# 3_Communication.net
KiCad netlist of a schematic drawn in Altium Designer
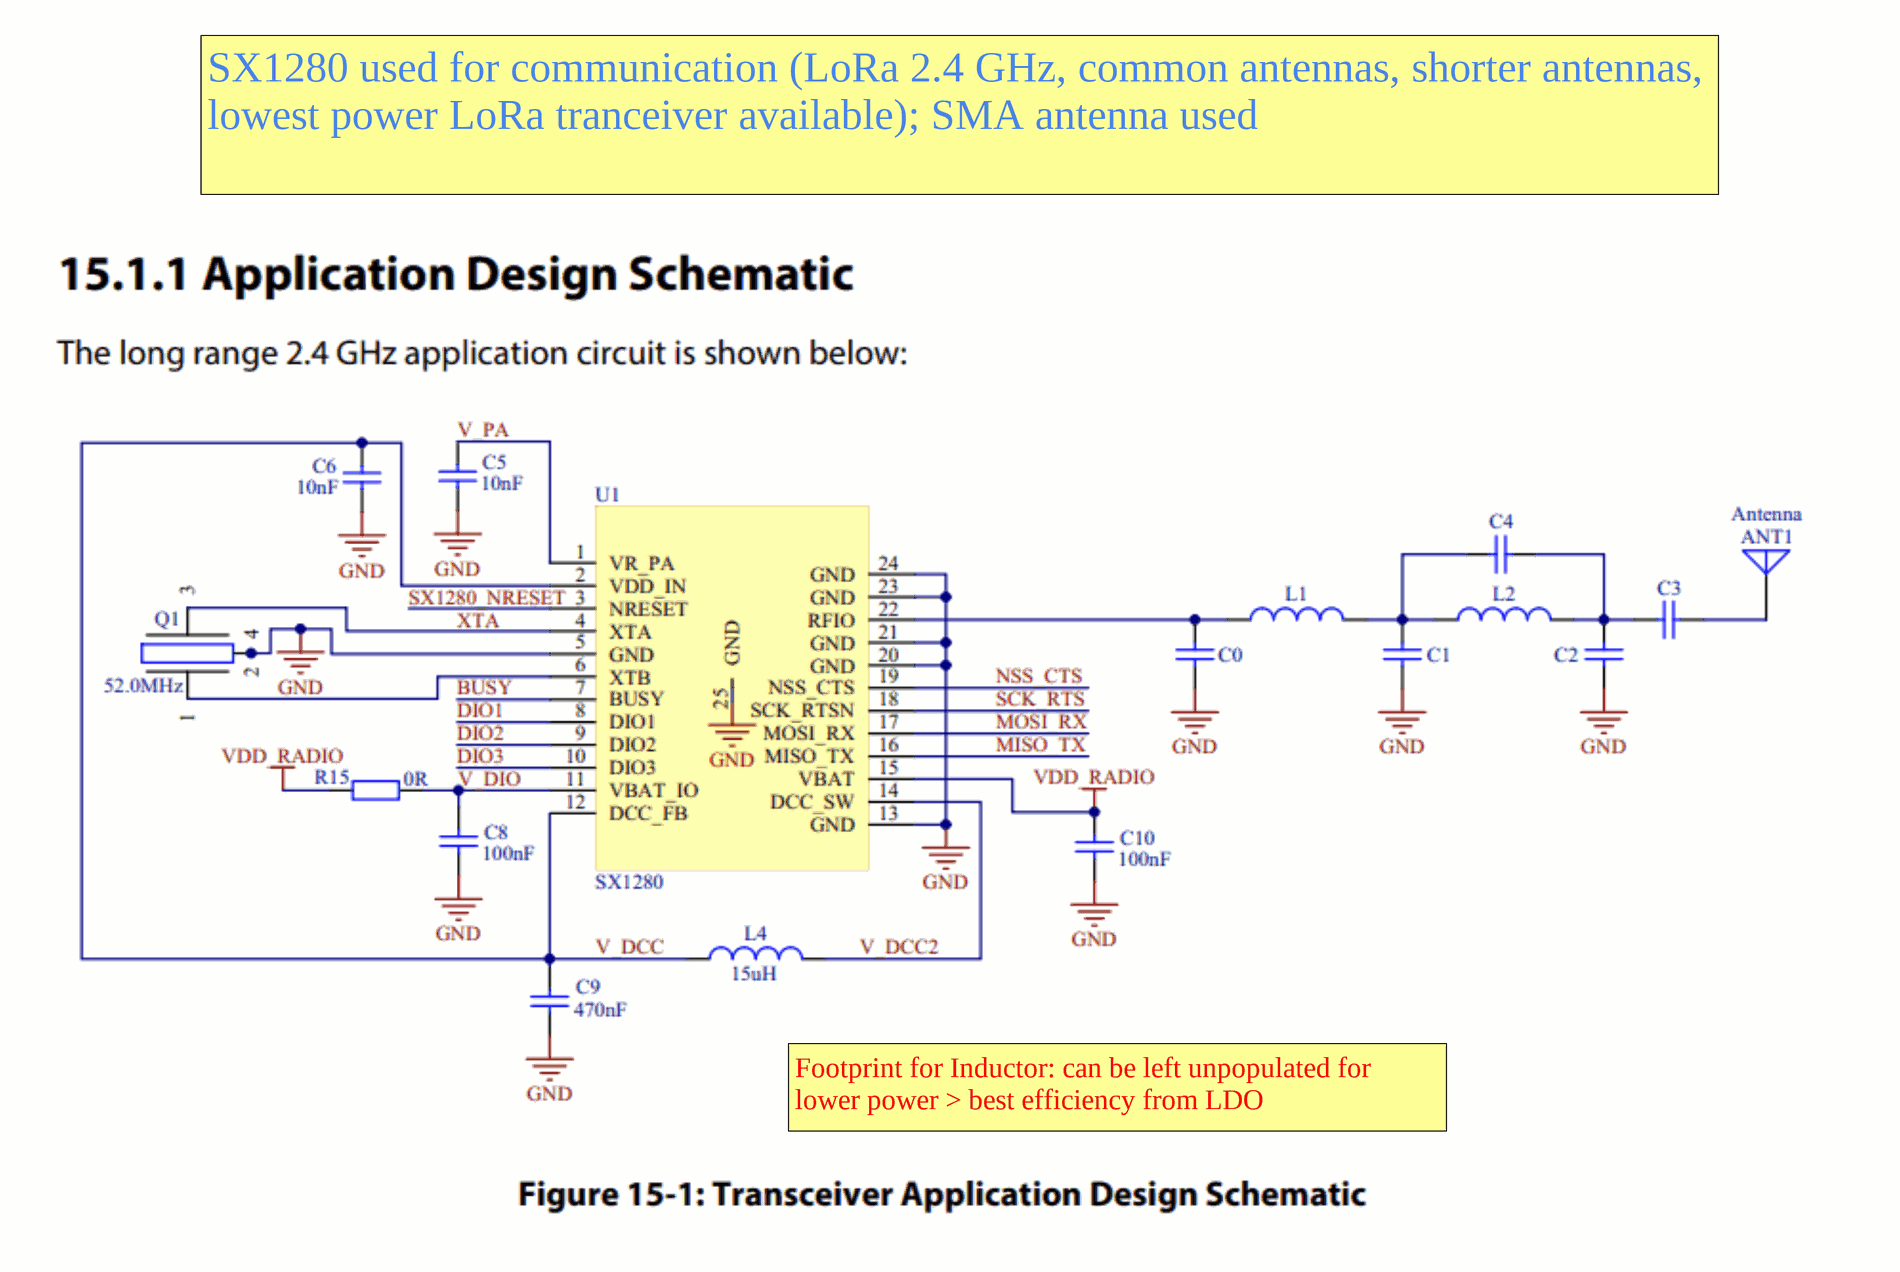
[diagram p0: 3_Communication.SchDoc, left]
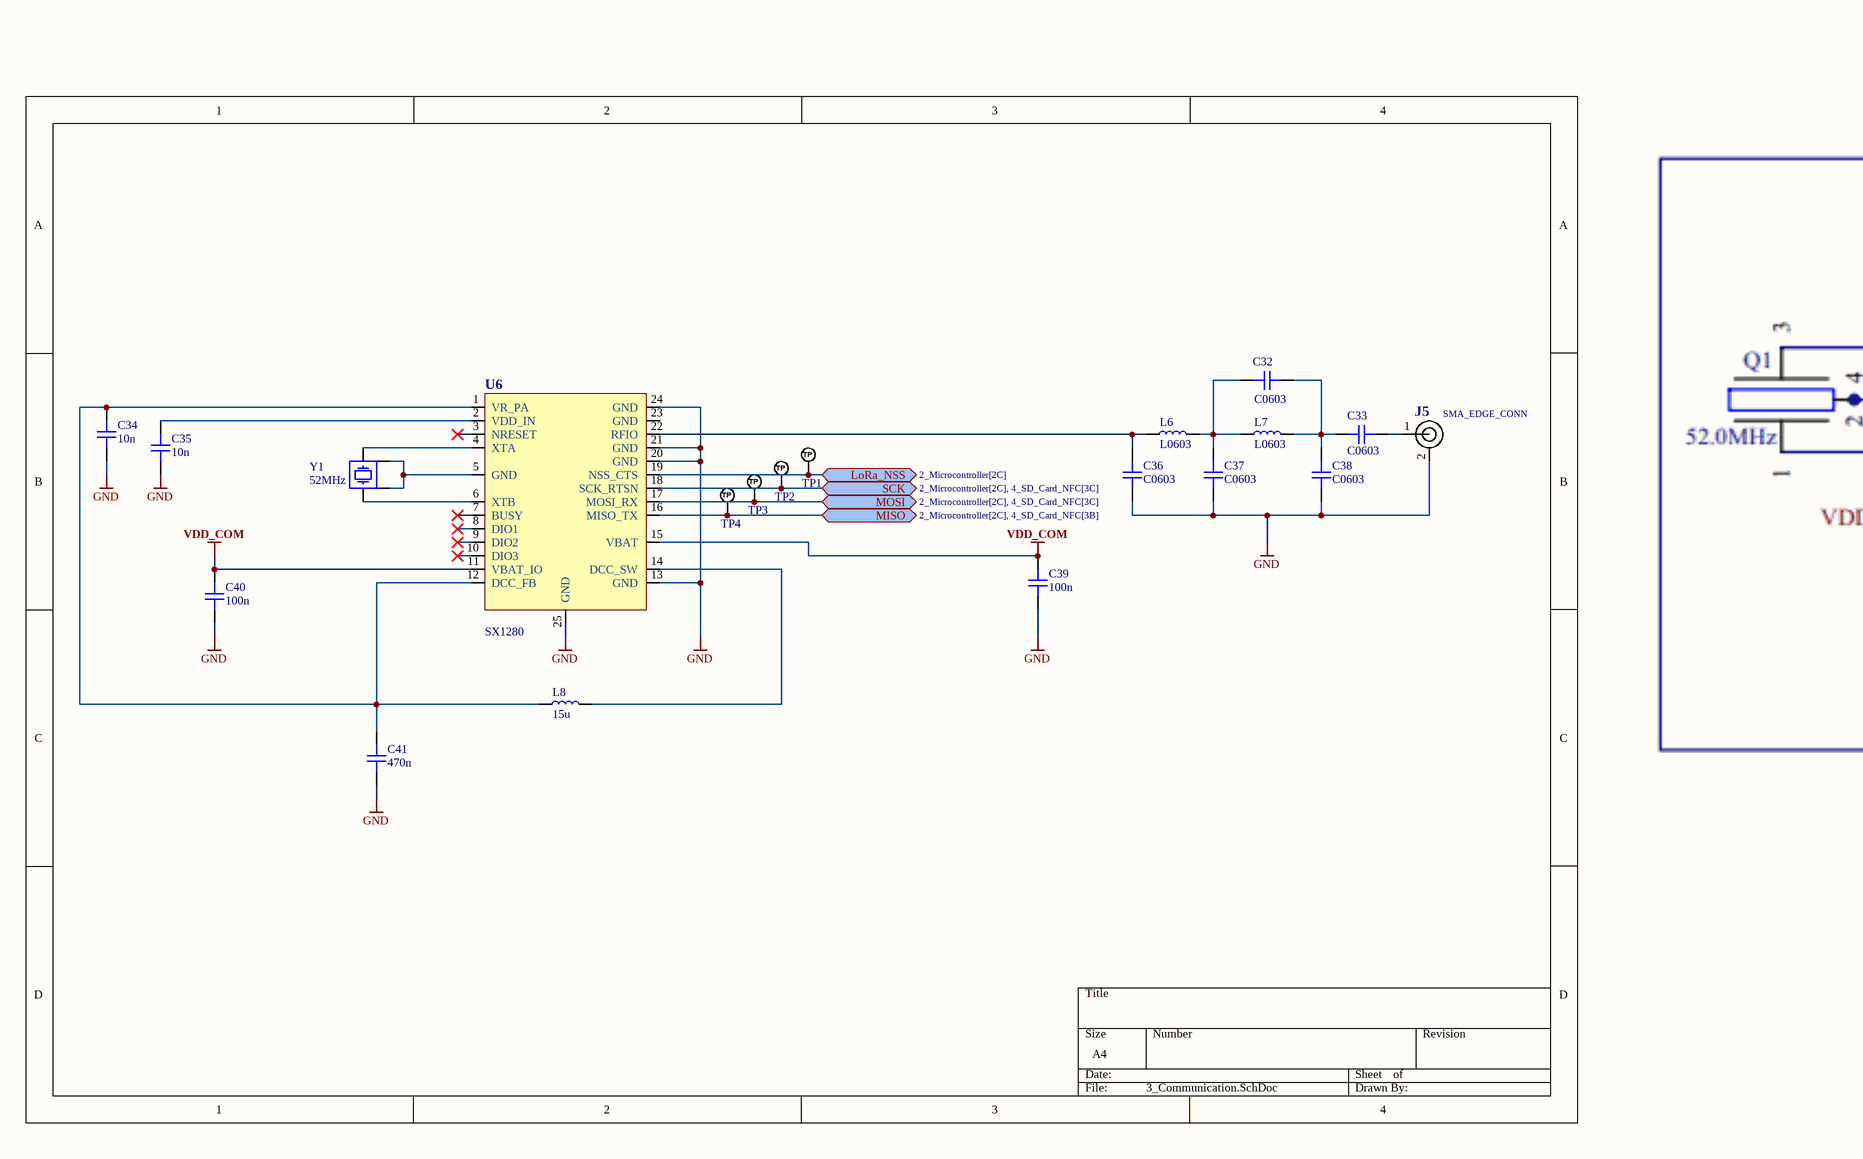
[diagram p1: 3_Communication.SchDoc, middle]
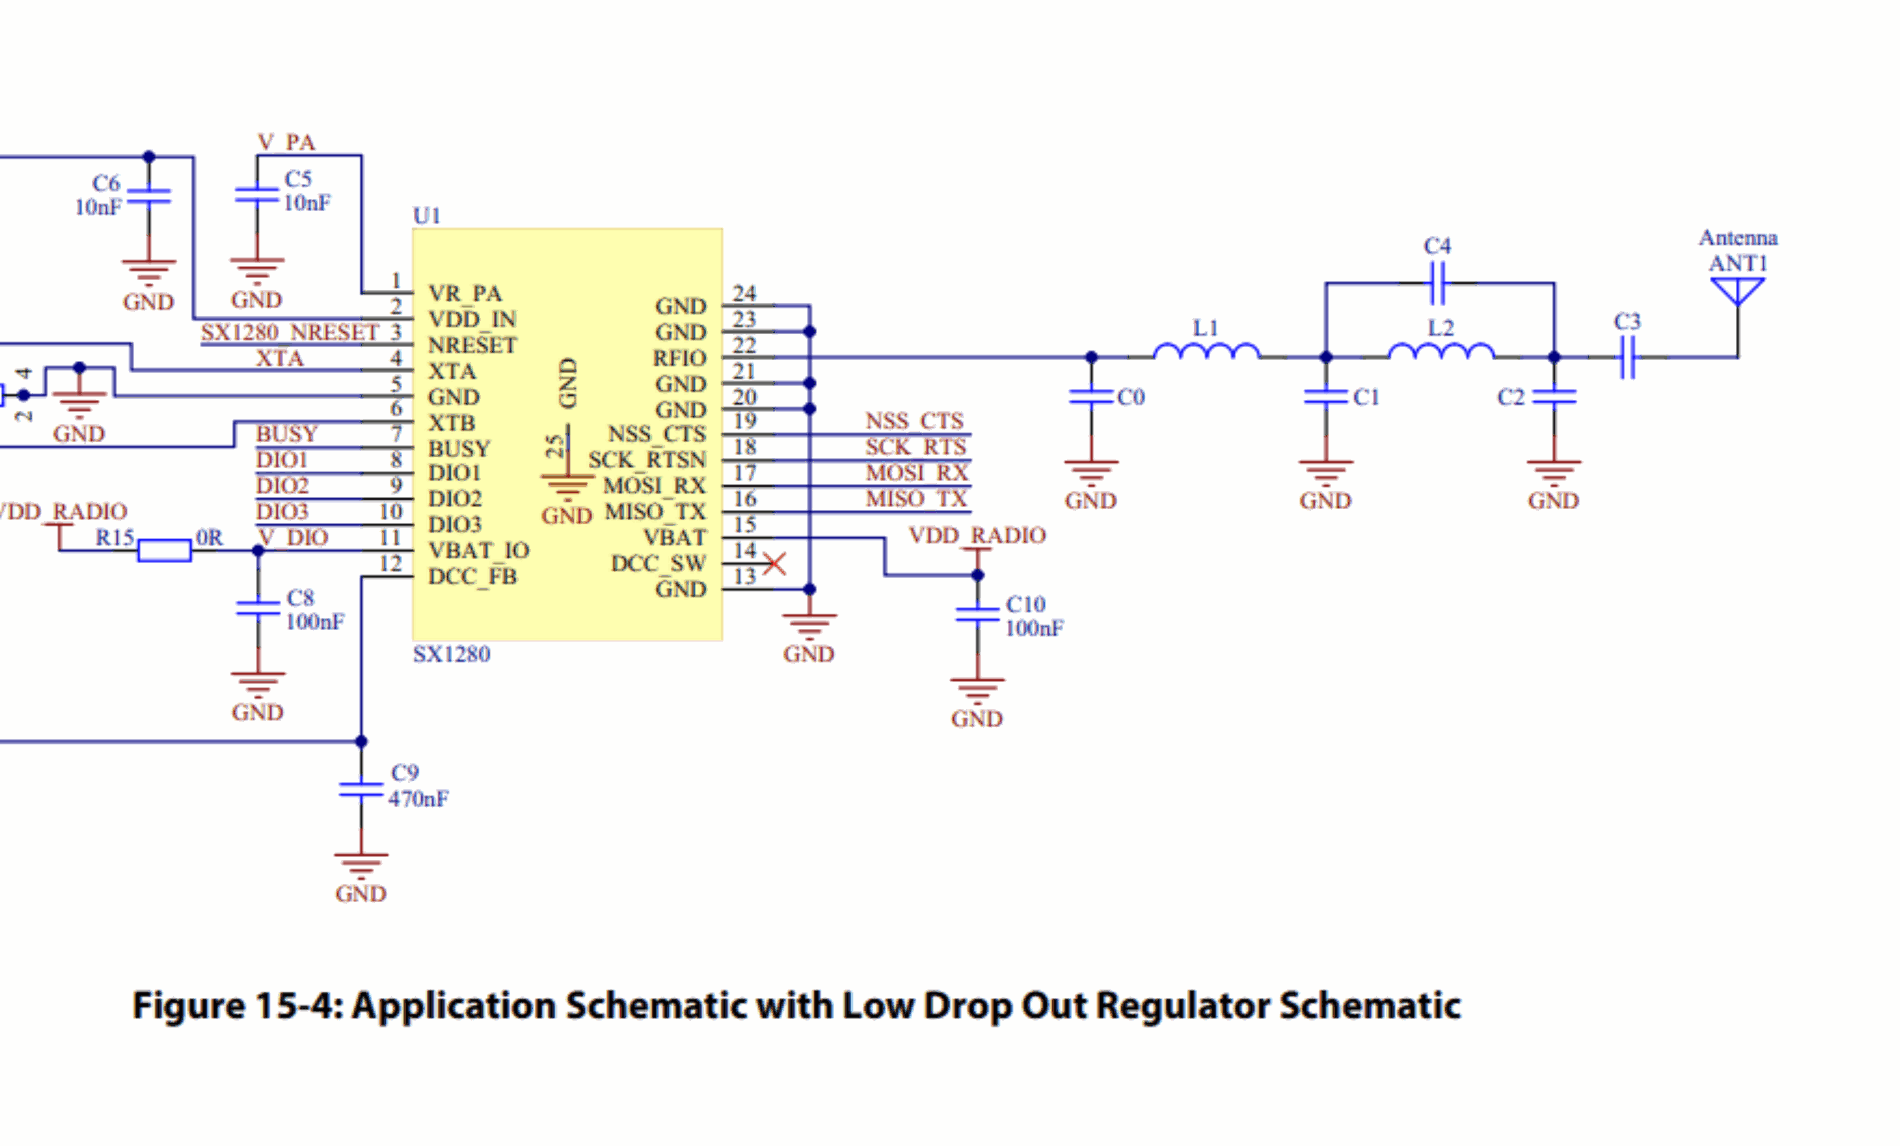
[diagram p2: 3_Communication.SchDoc, right]

(export (version "E")
  (design (tool "Eeschema 10.0.6"))
  (components
    (comp (ref "C32")
      (value "C0603")
      (footprint "CAP_0603")
      (description "Capacitor SMD 0603")
      (libsource (lib "Schlib_H2") (part "CAP_0603"))
    )
    (comp (ref "C33")
      (value "C0603")
      (footprint "CAP_0603")
      (description "Capacitor SMD 0603")
      (libsource (lib "Schlib_H2") (part "CAP_0603"))
    )
    (comp (ref "C34")
      (value "10n")
      (footprint "CAP_0603")
      (description "Capacitor SMD 0603")
      (libsource (lib "Schlib_H2") (part "CAP_0603"))
    )
    (comp (ref "C35")
      (value "10n")
      (footprint "CAP_0603")
      (description "Capacitor SMD 0603")
      (libsource (lib "Schlib_H2") (part "CAP_0603"))
    )
    (comp (ref "C36")
      (value "C0603")
      (footprint "CAP_0603")
      (description "Capacitor SMD 0603")
      (libsource (lib "Schlib_H2") (part "CAP_0603"))
    )
    (comp (ref "C37")
      (value "C0603")
      (footprint "CAP_0603")
      (description "Capacitor SMD 0603")
      (libsource (lib "Schlib_H2") (part "CAP_0603"))
    )
    (comp (ref "C38")
      (value "C0603")
      (footprint "CAP_0603")
      (description "Capacitor SMD 0603")
      (libsource (lib "Schlib_H2") (part "CAP_0603"))
    )
    (comp (ref "C39")
      (value "100n")
      (footprint "CAP_0603")
      (description "Capacitor SMD 0603")
      (libsource (lib "Schlib_H2") (part "CAP_0603"))
    )
    (comp (ref "C40")
      (value "100n")
      (footprint "CAP_0603")
      (description "Capacitor SMD 0603")
      (libsource (lib "Schlib_H2") (part "CAP_0603"))
    )
    (comp (ref "C41")
      (value "470n")
      (footprint "CAP_0603")
      (description "Capacitor SMD 0603")
      (libsource (lib "Schlib_H2") (part "CAP_0603"))
    )
    (comp (ref "J5")
      (value "SMA_EDGE_CONN")
      (footprint "CON-SMA-EDGE-S")
      (description "RF Connector SMA Female 50 Ohms 18 GHz PCB Edge Mount")
      (fields
        (field (name "MANUFACTURER") "RF Solutions")
        (field (name "MANUFACTURER PART NUMBER") "CON-SMA-EDGE-S")
      )
      (libsource (lib "Schlib_H2") (part "CON-SMA-EDGE-S"))
    )
    (comp (ref "L6")
      (value "L0603")
      (footprint "IND_0603")
      (description "Inductor SMD 0603")
      (libsource (lib "Schlib_H2") (part "IND_0603"))
    )
    (comp (ref "L7")
      (value "L0603")
      (footprint "IND_0603")
      (description "Inductor SMD 0603")
      (libsource (lib "Schlib_H2") (part "IND_0603"))
    )
    (comp (ref "L8")
      (value "15u")
      (footprint "IND_0603")
      (description "Inductor SMD 0603")
      (libsource (lib "Schlib_H2") (part "IND_0603"))
    )
    (comp (ref "TP1")
      (value "TP_NOBOM")
      (footprint "PAD_RND_1MM")
      (description "Test Point Round 1mm (NO BOM)")
      (libsource (lib "Schlib_H2") (part "TEST_POINT_RND_1MM"))
    )
    (comp (ref "TP2")
      (value "TP_NOBOM")
      (footprint "PAD_RND_1MM")
      (description "Test Point Round 1mm (NO BOM)")
      (libsource (lib "Schlib_H2") (part "TEST_POINT_RND_1MM"))
    )
    (comp (ref "TP3")
      (value "TP_NOBOM")
      (footprint "PAD_RND_1MM")
      (description "Test Point Round 1mm (NO BOM)")
      (libsource (lib "Schlib_H2") (part "TEST_POINT_RND_1MM"))
    )
    (comp (ref "TP4")
      (value "TP_NOBOM")
      (footprint "PAD_RND_1MM")
      (description "Test Point Round 1mm (NO BOM)")
      (libsource (lib "Schlib_H2") (part "TEST_POINT_RND_1MM"))
    )
    (comp (ref "U6")
      (value "SX1280")
      (description "Low power LoRa transceiver operating at 2.4GHz with ranging capability")
      (libsource (lib "Schlib_H2") (part "SX1280"))
    )
    (comp (ref "Y1")
      (value "52MHz")
      (footprint "XTAL_3225")
      (description "Crystal")
      (fields
        (field (name "MANUFACTURER") "Epson")
        (field (name "MANUFACTURER PART NUMBER") "TSX-3225 24.0000MF15X-AC")
      )
      (libsource (lib "Schlib_H2") (part "Crystal"))
    )
  )
  (nets
    (net (code "1") (name "/LoRa_NSS") (class "Default")
      (node (ref "TP1") (pin "1") (pinfunction "TP_1") (pintype "passive"))
      (node (ref "U6") (pin "19") (pinfunction "NSS_CTS_19") (pintype "passive"))
    )
    (net (code "2") (name "/MISO") (class "Default")
      (node (ref "TP4") (pin "1") (pinfunction "TP_1") (pintype "passive"))
      (node (ref "U6") (pin "16") (pinfunction "MISO_TX_16") (pintype "passive"))
    )
    (net (code "3") (name "/MOSI") (class "Default")
      (node (ref "TP3") (pin "1") (pinfunction "TP_1") (pintype "passive"))
      (node (ref "U6") (pin "17") (pinfunction "MOSI_RX_17") (pintype "passive"))
    )
    (net (code "4") (name "/SCK") (class "Default")
      (node (ref "TP2") (pin "1") (pinfunction "TP_1") (pintype "passive"))
      (node (ref "U6") (pin "18") (pinfunction "SCK_RTSN_18") (pintype "passive"))
    )
    (net (code "5") (name "GND") (class "Default")
      (node (ref "C34") (pin "1") (pinfunction "1_1") (pintype "passive"))
      (node (ref "C35") (pin "1") (pinfunction "1_1") (pintype "passive"))
      (node (ref "C36") (pin "1") (pinfunction "1_1") (pintype "passive"))
      (node (ref "C37") (pin "1") (pinfunction "1_1") (pintype "passive"))
      (node (ref "C38") (pin "1") (pinfunction "1_1") (pintype "passive"))
      (node (ref "C39") (pin "1") (pinfunction "1_1") (pintype "passive"))
      (node (ref "C40") (pin "1") (pinfunction "1_1") (pintype "passive"))
      (node (ref "C41") (pin "1") (pinfunction "1_1") (pintype "passive"))
      (node (ref "J5") (pin "2") (pinfunction "2_2") (pintype "passive"))
      (node (ref "U6") (pin "13") (pinfunction "GND_13") (pintype "passive"))
      (node (ref "U6") (pin "20") (pinfunction "GND_20") (pintype "passive"))
      (node (ref "U6") (pin "21") (pinfunction "GND_21") (pintype "passive"))
      (node (ref "U6") (pin "24") (pinfunction "GND_24") (pintype "passive"))
      (node (ref "U6") (pin "25") (pinfunction "GND_25") (pintype "passive"))
    )
    (net (code "6") (name "Net-(C32-Pad1)") (class "Default")
      (node (ref "C32") (pin "1") (pinfunction "1_1") (pintype "passive"))
      (node (ref "C33") (pin "2") (pinfunction "2_2") (pintype "passive"))
      (node (ref "C38") (pin "2") (pinfunction "2_2") (pintype "passive"))
      (node (ref "L7") (pin "2") (pinfunction "2_2") (pintype "passive"))
    )
    (net (code "7") (name "Net-(C32-Pad2)") (class "Default")
      (node (ref "C32") (pin "2") (pinfunction "2_2") (pintype "passive"))
      (node (ref "C37") (pin "2") (pinfunction "2_2") (pintype "passive"))
      (node (ref "L6") (pin "2") (pinfunction "2_2") (pintype "passive"))
      (node (ref "L7") (pin "1") (pinfunction "1_1") (pintype "passive"))
    )
    (net (code "8") (name "Net-(C33-Pad1)") (class "Default")
      (node (ref "C33") (pin "1") (pinfunction "1_1") (pintype "passive"))
      (node (ref "J5") (pin "1") (pinfunction "1_1") (pintype "passive"))
    )
    (net (code "9") (name "Net-(U6-DCC_FB)") (class "Default")
      (node (ref "C34") (pin "2") (pinfunction "2_2") (pintype "passive"))
      (node (ref "C41") (pin "2") (pinfunction "2_2") (pintype "passive"))
      (node (ref "L8") (pin "1") (pinfunction "1_1") (pintype "passive"))
      (node (ref "U6") (pin "1") (pinfunction "VR_PA_1") (pintype "passive"))
      (node (ref "U6") (pin "12") (pinfunction "DCC_FB_12") (pintype "passive"))
    )
    (net (code "10") (name "Net-(U6-DCC_SW)") (class "Default")
      (node (ref "L8") (pin "2") (pinfunction "2_2") (pintype "passive"))
      (node (ref "U6") (pin "14") (pinfunction "DCC_SW_14") (pintype "passive"))
    )
    (net (code "11") (name "Net-(U6-GND-Pad5)") (class "Default")
      (node (ref "U6") (pin "5") (pinfunction "GND_5") (pintype "passive"))
      (node (ref "Y1") (pin "2") (pinfunction "2_2") (pintype "passive"))
      (node (ref "Y1") (pin "4") (pinfunction "4_4") (pintype "passive"))
    )
    (net (code "12") (name "Net-(U6-RFIO)") (class "Default")
      (node (ref "C36") (pin "2") (pinfunction "2_2") (pintype "passive"))
      (node (ref "L6") (pin "1") (pinfunction "1_1") (pintype "passive"))
      (node (ref "U6") (pin "22") (pinfunction "RFIO_22") (pintype "passive"))
    )
    (net (code "13") (name "Net-(U6-VDD_IN)") (class "Default")
      (node (ref "C35") (pin "2") (pinfunction "2_2") (pintype "passive"))
      (node (ref "U6") (pin "2") (pinfunction "VDD_IN_2") (pintype "passive"))
    )
    (net (code "14") (name "Net-(U6-XTA)") (class "Default")
      (node (ref "U6") (pin "4") (pinfunction "XTA_4") (pintype "passive"))
      (node (ref "Y1") (pin "3") (pinfunction "3_3") (pintype "passive"))
    )
    (net (code "15") (name "Net-(U6-XTB)") (class "Default")
      (node (ref "U6") (pin "6") (pinfunction "XTB_6") (pintype "passive"))
      (node (ref "Y1") (pin "1") (pinfunction "1_1") (pintype "passive"))
    )
    (net (code "16") (name "VDD_COM") (class "Default")
      (node (ref "C39") (pin "2") (pinfunction "2_2") (pintype "passive"))
      (node (ref "C40") (pin "2") (pinfunction "2_2") (pintype "passive"))
      (node (ref "U6") (pin "11") (pinfunction "VBAT_IO_11") (pintype "passive"))
      (node (ref "U6") (pin "15") (pinfunction "VBAT_15") (pintype "passive"))
    )
    (net (code "17") (name "unconnected-(U6-BUSY-Pad7)") (class "Default")
      (node (ref "U6") (pin "7") (pinfunction "BUSY_7") (pintype "passive+no_connect"))
    )
    (net (code "18") (name "unconnected-(U6-DIO1-Pad8)") (class "Default")
      (node (ref "U6") (pin "8") (pinfunction "DIO1_8") (pintype "passive+no_connect"))
    )
    (net (code "19") (name "unconnected-(U6-DIO2-Pad9)") (class "Default")
      (node (ref "U6") (pin "9") (pinfunction "DIO2_9") (pintype "passive+no_connect"))
    )
    (net (code "20") (name "unconnected-(U6-DIO3-Pad10)") (class "Default")
      (node (ref "U6") (pin "10") (pinfunction "DIO3_10") (pintype "passive+no_connect"))
    )
    (net (code "21") (name "unconnected-(U6-GND-Pad23)") (class "Default")
      (node (ref "U6") (pin "23") (pinfunction "GND_23") (pintype "passive"))
    )
    (net (code "22") (name "unconnected-(U6-NRESET-Pad3)") (class "Default")
      (node (ref "U6") (pin "3") (pinfunction "NRESET_3") (pintype "passive+no_connect"))
    )
  )
)
